# redresseur.net
KiCad netlist of a schematic drawn in Altium Designer
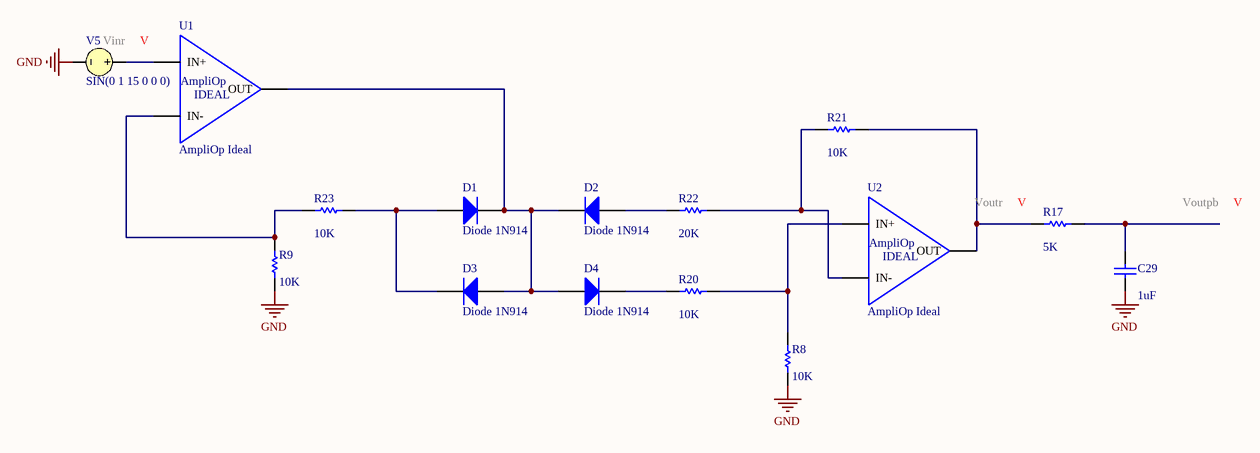
[diagram p0: redresseur.SchDoc]

(export (version "E")
  (design (tool "Eeschema 10.0.6"))
  (components
    (comp (ref "C29")
      (value "1uF")
      (footprint "RAD-0.3")
      (description "Capacitor")
      (fields (field (name "Comment") "Cap") (field (name "PUBLISHER") "Altium Limited"))
      (libsource (lib "Miscellaneous Devices") (part "Cap"))
    )
    (comp (ref "D1")
      (value "Diode 1N914")
      (footprint "DO-35")
      (description "High Conductance Fast Diode")
      (fields (field (name "PUBLISHER") "Altium Limited"))
      (libsource (lib "Miscellaneous Devices") (part "Diode 1N914"))
    )
    (comp (ref "D2")
      (value "Diode 1N914")
      (footprint "DO-35")
      (description "High Conductance Fast Diode")
      (fields (field (name "PUBLISHER") "Altium Limited"))
      (libsource (lib "Miscellaneous Devices") (part "Diode 1N914"))
    )
    (comp (ref "D3")
      (value "Diode 1N914")
      (footprint "DO-35")
      (description "High Conductance Fast Diode")
      (fields (field (name "PUBLISHER") "Altium Limited"))
      (libsource (lib "Miscellaneous Devices") (part "Diode 1N914"))
    )
    (comp (ref "D4")
      (value "Diode 1N914")
      (footprint "DO-35")
      (description "High Conductance Fast Diode")
      (fields (field (name "PUBLISHER") "Altium Limited"))
      (libsource (lib "Miscellaneous Devices") (part "Diode 1N914"))
    )
    (comp (ref "R8")
      (value "10K")
      (footprint "AXIAL-0.3")
      (description "Resistor")
      (fields (field (name "Comment") "Res1") (field (name "PUBLISHER") "Altium Limited"))
      (libsource (lib "Miscellaneous Devices") (part "Res1"))
    )
    (comp (ref "R9")
      (value "10K")
      (footprint "AXIAL-0.3")
      (description "Resistor")
      (fields (field (name "Comment") "Res1") (field (name "PUBLISHER") "Altium Limited"))
      (libsource (lib "Miscellaneous Devices") (part "Res1"))
    )
    (comp (ref "R17")
      (value "5K")
      (footprint "AXIAL-0.3")
      (description "Resistor")
      (fields (field (name "Comment") "Res1") (field (name "PUBLISHER") "Altium Limited"))
      (libsource (lib "Miscellaneous Devices") (part "Res1"))
    )
    (comp (ref "R20")
      (value "10K")
      (footprint "AXIAL-0.3")
      (description "Resistor")
      (fields (field (name "Comment") "Res1") (field (name "PUBLISHER") "Altium Limited"))
      (libsource (lib "Miscellaneous Devices") (part "Res1"))
    )
    (comp (ref "R21")
      (value "10K")
      (footprint "AXIAL-0.3")
      (description "Resistor")
      (fields (field (name "Comment") "Res1") (field (name "PUBLISHER") "Altium Limited"))
      (libsource (lib "Miscellaneous Devices") (part "Res1"))
    )
    (comp (ref "R22")
      (value "20K")
      (footprint "AXIAL-0.3")
      (description "Resistor")
      (fields (field (name "Comment") "Res1") (field (name "PUBLISHER") "Altium Limited"))
      (libsource (lib "Miscellaneous Devices") (part "Res1"))
    )
    (comp (ref "R23")
      (value "10K")
      (footprint "AXIAL-0.3")
      (description "Resistor")
      (fields (field (name "Comment") "Res1") (field (name "PUBLISHER") "Altium Limited"))
      (libsource (lib "Miscellaneous Devices") (part "Res1"))
    )
    (comp (ref "U1") (value "AmpliOp Ideal") (libsource (lib "Librarie_S2") (part "AmpliOp_ideal")))
    (comp (ref "U2") (value "AmpliOp Ideal") (libsource (lib "Librarie_S2") (part "AmpliOp_ideal")))
    (comp (ref "V5")
      (value "SIN(0 1 15 0 0 0)")
      (description "Voltage Source")
      (fields (field (name "PUBLISHER") "Altium Limited"))
      (libsource (lib "Simulation Sources") (part "VSRC"))
    )
  )
  (nets
    (net (code "1") (name "GND") (class "Default")
      (node (ref "C29") (pin "1") (pinfunction "1_1") (pintype "passive"))
      (node (ref "R8") (pin "1") (pinfunction "1_1") (pintype "passive"))
      (node (ref "R9") (pin "1") (pinfunction "1_1") (pintype "passive"))
      (node (ref "V5") (pin "2") (pinfunction "2_2") (pintype "passive"))
    )
    (net (code "2") (name "Net-(C29-Pad2)") (class "Default")
      (node (ref "C29") (pin "2") (pinfunction "2_2") (pintype "passive"))
      (node (ref "R17") (pin "2") (pinfunction "2_2") (pintype "passive"))
    )
    (net (code "3") (name "Net-(D1-A)") (class "Default")
      (node (ref "D1") (pin "1") (pinfunction "A_1") (pintype "passive"))
      (node (ref "D3") (pin "2") (pinfunction "K_2") (pintype "passive"))
      (node (ref "R23") (pin "2") (pinfunction "2_2") (pintype "passive"))
    )
    (net (code "4") (name "Net-(D1-K)") (class "Default")
      (node (ref "D1") (pin "2") (pinfunction "K_2") (pintype "passive"))
      (node (ref "D2") (pin "2") (pinfunction "K_2") (pintype "passive"))
      (node (ref "D3") (pin "1") (pinfunction "A_1") (pintype "passive"))
      (node (ref "D4") (pin "1") (pinfunction "A_1") (pintype "passive"))
      (node (ref "U1") (pin "3") (pinfunction "OUT_3") (pintype "passive"))
    )
    (net (code "5") (name "Net-(D2-A)") (class "Default")
      (node (ref "D2") (pin "1") (pinfunction "A_1") (pintype "passive"))
      (node (ref "R22") (pin "1") (pinfunction "1_1") (pintype "passive"))
    )
    (net (code "6") (name "Net-(D4-K)") (class "Default")
      (node (ref "D4") (pin "2") (pinfunction "K_2") (pintype "passive"))
      (node (ref "R20") (pin "1") (pinfunction "1_1") (pintype "passive"))
    )
    (net (code "7") (name "Net-(U1-IN+)") (class "Default")
      (node (ref "U1") (pin "1") (pinfunction "IN+_1") (pintype "passive"))
      (node (ref "V5") (pin "1") (pinfunction "1_1") (pintype "passive"))
    )
    (net (code "8") (name "Net-(U1-IN-)") (class "Default")
      (node (ref "R23") (pin "1") (pinfunction "1_1") (pintype "passive"))
      (node (ref "R9") (pin "2") (pinfunction "2_2") (pintype "passive"))
      (node (ref "U1") (pin "2") (pinfunction "IN-_2") (pintype "passive"))
    )
    (net (code "9") (name "Net-(U2-IN+)") (class "Default")
      (node (ref "R20") (pin "2") (pinfunction "2_2") (pintype "passive"))
      (node (ref "R8") (pin "2") (pinfunction "2_2") (pintype "passive"))
      (node (ref "U2") (pin "1") (pinfunction "IN+_1") (pintype "passive"))
    )
    (net (code "10") (name "Net-(U2-IN-)") (class "Default")
      (node (ref "R21") (pin "1") (pinfunction "1_1") (pintype "passive"))
      (node (ref "R22") (pin "2") (pinfunction "2_2") (pintype "passive"))
      (node (ref "U2") (pin "2") (pinfunction "IN-_2") (pintype "passive"))
    )
    (net (code "11") (name "Net-(U2-OUT)") (class "Default")
      (node (ref "R17") (pin "1") (pinfunction "1_1") (pintype "passive"))
      (node (ref "R21") (pin "2") (pinfunction "2_2") (pintype "passive"))
      (node (ref "U2") (pin "3") (pinfunction "OUT_3") (pintype "passive"))
    )
  )
)
